# MCU.net
KiCad netlist of a schematic drawn in Altium Designer
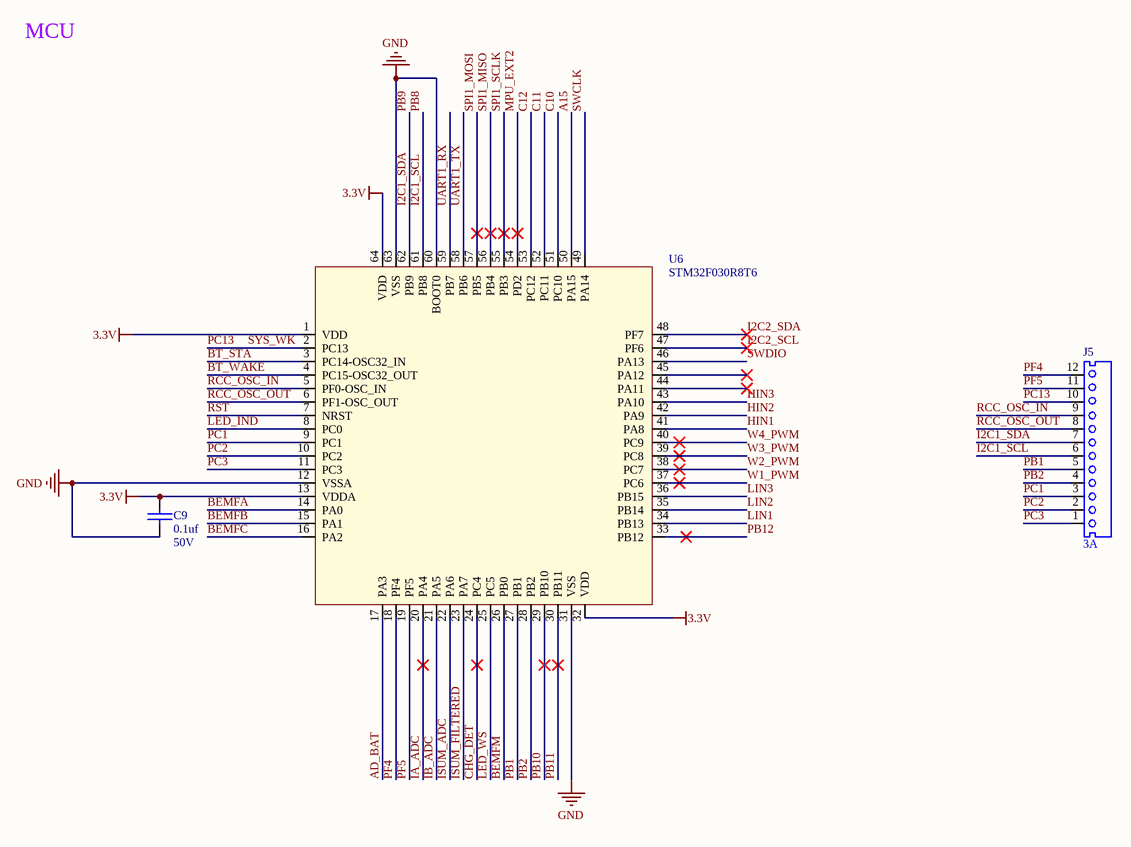
[diagram p0: MCU.SchDoc]

(export (version "E")
  (design (tool "Eeschema 10.0.6"))
  (components
    (comp (ref "C9")
      (value "0.1uf")
      (footprint "CAPC0603-RW")
      (description "GP CHIP CAP 0.015uF 50V 10% 0603 TYPE X7R")
      (fields
        (field (name "TOLERANCE") "10%")
        (field (name "VOLTAGE") "50V")
        (field (name "Comment") "PXL456470-1530")
      )
      (libsource (lib "P-Capacitors") (part "CAP0603 0.015uF 50V 10%"))
    )
    (comp (ref "J5")
      (value "T690300029300")
      (footprint "CONN 12P PH=2.5 ST HAA250A-12A")
      (description "CONNECTOR 12 PIN P:2.5MM P2.54-12 K")
      (fields
        (field (name "MFG") "金科基")
        (field (name "MFG PART") "HAA250A-12A")
        (field (name "CURRENT") "3A")
        (field (name "CREATE_NAME") "Nathan")
      )
      (libsource (lib "C-Connector") (part "CONN 12P PH=2.5 ST HAA250A-12A"))
    )
    (comp (ref "U6")
      (value "T610300097225")
      (footprint "QFP50P1200X1200X160-64N")
      (description "MCU STM32F030RCT6TR LQFP64 ST K")
      (fields
        (field (name "MFG") "ST     (STM意法半導體)")
        (field (name "MFG PART") "STM32F030R8T6")
        (field (name "CREATE_NAME") "Nathan")
      )
      (libsource (lib "R-Semiconductors") (part "STM32F030RCT6TR"))
    )
  )
  (nets
    (net (code "1") (name "/A15") (class "Default")
      (node (ref "U6") (pin "50") (pinfunction "PA15_50") (pintype "passive"))
    )
    (net (code "2") (name "/AD_BAT") (class "Default")
      (node (ref "U6") (pin "17") (pinfunction "PA3_17") (pintype "passive"))
    )
    (net (code "3") (name "/BEMFA") (class "Default")
      (node (ref "U6") (pin "14") (pinfunction "PA0_14") (pintype "passive"))
    )
    (net (code "4") (name "/BEMFB") (class "Default")
      (node (ref "U6") (pin "15") (pinfunction "PA1_15") (pintype "passive"))
    )
    (net (code "5") (name "/BEMFC") (class "Default")
      (node (ref "U6") (pin "16") (pinfunction "PA2_16") (pintype "passive"))
    )
    (net (code "6") (name "/BEMFM") (class "Default")
      (node (ref "U6") (pin "26") (pinfunction "PB0_26") (pintype "passive"))
    )
    (net (code "7") (name "/BT_STA") (class "Default")
      (node (ref "U6") (pin "3") (pinfunction "PC14-OSC32_IN_3") (pintype "passive"))
    )
    (net (code "8") (name "/BT_WAKE") (class "Default")
      (node (ref "U6") (pin "4") (pinfunction "PC15-OSC32_OUT_4") (pintype "passive"))
    )
    (net (code "9") (name "/C10") (class "Default")
      (node (ref "U6") (pin "51") (pinfunction "PC10_51") (pintype "passive"))
    )
    (net (code "10") (name "/C11") (class "Default")
      (node (ref "U6") (pin "52") (pinfunction "PC11_52") (pintype "passive"))
    )
    (net (code "11") (name "/C12") (class "Default")
      (node (ref "U6") (pin "53") (pinfunction "PC12_53") (pintype "passive"))
    )
    (net (code "12") (name "/CHG_DET") (class "Default")
      (node (ref "U6") (pin "24") (pinfunction "PC4_24") (pintype "passive"))
    )
    (net (code "13") (name "/HIN1") (class "Default")
      (node (ref "U6") (pin "41") (pinfunction "PA8_41") (pintype "passive"))
    )
    (net (code "14") (name "/HIN2") (class "Default")
      (node (ref "U6") (pin "42") (pinfunction "PA9_42") (pintype "passive"))
    )
    (net (code "15") (name "/HIN3") (class "Default")
      (node (ref "U6") (pin "43") (pinfunction "PA10_43") (pintype "passive"))
    )
    (net (code "16") (name "/I2C1_SCL") (class "Default")
      (node (ref "J5") (pin "6") (pinfunction "6_6") (pintype "passive"))
      (node (ref "U6") (pin "61") (pinfunction "PB8_61") (pintype "passive"))
    )
    (net (code "17") (name "/I2C1_SDA") (class "Default")
      (node (ref "J5") (pin "7") (pinfunction "7_7") (pintype "passive"))
      (node (ref "U6") (pin "62") (pinfunction "PB9_62") (pintype "passive"))
    )
    (net (code "18") (name "/I2C2_SCL") (class "Default")
      (node (ref "U6") (pin "47") (pinfunction "PF6_47") (pintype "passive+no_connect"))
    )
    (net (code "19") (name "/I2C2_SDA") (class "Default")
      (node (ref "U6") (pin "48") (pinfunction "PF7_48") (pintype "passive+no_connect"))
    )
    (net (code "20") (name "/IA_ADC") (class "Default")
      (node (ref "U6") (pin "20") (pinfunction "PA4_20") (pintype "passive"))
    )
    (net (code "21") (name "/IB_ADC") (class "Default")
      (node (ref "U6") (pin "21") (pinfunction "PA5_21") (pintype "passive"))
    )
    (net (code "22") (name "/ISUM_ADC") (class "Default")
      (node (ref "U6") (pin "22") (pinfunction "PA6_22") (pintype "passive"))
    )
    (net (code "23") (name "/ISUM_FILTERED") (class "Default")
      (node (ref "U6") (pin "23") (pinfunction "PA7_23") (pintype "passive"))
    )
    (net (code "24") (name "/LED_IND") (class "Default")
      (node (ref "U6") (pin "8") (pinfunction "PC0_8") (pintype "passive"))
    )
    (net (code "25") (name "/LED_WS") (class "Default")
      (node (ref "U6") (pin "25") (pinfunction "PC5_25") (pintype "passive"))
    )
    (net (code "26") (name "/LIN1") (class "Default")
      (node (ref "U6") (pin "34") (pinfunction "PB13_34") (pintype "passive"))
    )
    (net (code "27") (name "/LIN2") (class "Default")
      (node (ref "U6") (pin "35") (pinfunction "PB14_35") (pintype "passive"))
    )
    (net (code "28") (name "/LIN3") (class "Default")
      (node (ref "U6") (pin "36") (pinfunction "PB15_36") (pintype "passive"))
    )
    (net (code "29") (name "/MPU_EXT2") (class "Default")
      (node (ref "U6") (pin "54") (pinfunction "PD2_54") (pintype "passive"))
    )
    (net (code "30") (name "/PB1") (class "Default")
      (node (ref "J5") (pin "5") (pinfunction "5_5") (pintype "passive"))
      (node (ref "U6") (pin "27") (pinfunction "PB1_27") (pintype "passive"))
    )
    (net (code "31") (name "/PB2") (class "Default")
      (node (ref "J5") (pin "4") (pinfunction "4_4") (pintype "passive"))
      (node (ref "U6") (pin "28") (pinfunction "PB2_28") (pintype "passive"))
    )
    (net (code "32") (name "/PB10") (class "Default")
      (node (ref "U6") (pin "29") (pinfunction "PB10_29") (pintype "passive"))
    )
    (net (code "33") (name "/PB11") (class "Default")
      (node (ref "U6") (pin "30") (pinfunction "PB11_30") (pintype "passive"))
    )
    (net (code "34") (name "/PB12") (class "Default")
      (node (ref "U6") (pin "33") (pinfunction "PB12_33") (pintype "passive"))
    )
    (net (code "35") (name "/PC1") (class "Default")
      (node (ref "J5") (pin "3") (pinfunction "3_3") (pintype "passive"))
      (node (ref "U6") (pin "9") (pinfunction "PC1_9") (pintype "passive"))
    )
    (net (code "36") (name "/PC2") (class "Default")
      (node (ref "J5") (pin "2") (pinfunction "2_2") (pintype "passive"))
      (node (ref "U6") (pin "10") (pinfunction "PC2_10") (pintype "passive"))
    )
    (net (code "37") (name "/PC3") (class "Default")
      (node (ref "J5") (pin "1") (pinfunction "1_1") (pintype "passive"))
      (node (ref "U6") (pin "11") (pinfunction "PC3_11") (pintype "passive"))
    )
    (net (code "38") (name "/PC13") (class "Default")
      (node (ref "J5") (pin "10") (pinfunction "10_10") (pintype "passive"))
      (node (ref "U6") (pin "2") (pinfunction "PC13_2") (pintype "passive"))
    )
    (net (code "39") (name "/PF4") (class "Default")
      (node (ref "J5") (pin "12") (pinfunction "12_12") (pintype "passive"))
      (node (ref "U6") (pin "18") (pinfunction "PF4_18") (pintype "passive"))
    )
    (net (code "40") (name "/PF5") (class "Default")
      (node (ref "J5") (pin "11") (pinfunction "11_11") (pintype "passive"))
      (node (ref "U6") (pin "19") (pinfunction "PF5_19") (pintype "passive"))
    )
    (net (code "41") (name "/RCC_OSC_IN") (class "Default")
      (node (ref "J5") (pin "9") (pinfunction "9_9") (pintype "passive"))
      (node (ref "U6") (pin "5") (pinfunction "PF0-OSC_IN_5") (pintype "passive"))
    )
    (net (code "42") (name "/RCC_OSC_OUT") (class "Default")
      (node (ref "J5") (pin "8") (pinfunction "8_8") (pintype "passive"))
      (node (ref "U6") (pin "6") (pinfunction "PF1-OSC_OUT_6") (pintype "passive"))
    )
    (net (code "43") (name "/RST") (class "Default")
      (node (ref "U6") (pin "7") (pinfunction "NRST_7") (pintype "passive"))
    )
    (net (code "44") (name "/SPI1_MISO") (class "Default")
      (node (ref "U6") (pin "56") (pinfunction "PB4_56") (pintype "passive"))
    )
    (net (code "45") (name "/SPI1_MOSI") (class "Default")
      (node (ref "U6") (pin "57") (pinfunction "PB5_57") (pintype "passive"))
    )
    (net (code "46") (name "/SPI1_SCLK") (class "Default")
      (node (ref "U6") (pin "55") (pinfunction "PB3_55") (pintype "passive"))
    )
    (net (code "47") (name "/SWCLK") (class "Default")
      (node (ref "U6") (pin "49") (pinfunction "PA14_49") (pintype "passive"))
    )
    (net (code "48") (name "/SWDIO") (class "Default")
      (node (ref "U6") (pin "46") (pinfunction "PA13_46") (pintype "passive"))
    )
    (net (code "49") (name "/UART1_RX") (class "Default")
      (node (ref "U6") (pin "59") (pinfunction "PB7_59") (pintype "passive"))
    )
    (net (code "50") (name "/UART1_TX") (class "Default")
      (node (ref "U6") (pin "58") (pinfunction "PB6_58") (pintype "passive"))
    )
    (net (code "51") (name "/W1_PWM") (class "Default")
      (node (ref "U6") (pin "37") (pinfunction "PC6_37") (pintype "passive"))
    )
    (net (code "52") (name "/W2_PWM") (class "Default")
      (node (ref "U6") (pin "38") (pinfunction "PC7_38") (pintype "passive"))
    )
    (net (code "53") (name "/W3_PWM") (class "Default")
      (node (ref "U6") (pin "39") (pinfunction "PC8_39") (pintype "passive"))
    )
    (net (code "54") (name "/W4_PWM") (class "Default")
      (node (ref "U6") (pin "40") (pinfunction "PC9_40") (pintype "passive"))
    )
    (net (code "55") (name "3.3V") (class "Default")
      (node (ref "C9") (pin "2") (pinfunction "2_2") (pintype "passive"))
      (node (ref "U6") (pin "1") (pinfunction "VDD_1") (pintype "passive"))
      (node (ref "U6") (pin "13") (pinfunction "VDDA_13") (pintype "passive"))
      (node (ref "U6") (pin "32") (pinfunction "VDD_32") (pintype "passive"))
      (node (ref "U6") (pin "64") (pinfunction "VDD_64") (pintype "passive"))
    )
    (net (code "56") (name "GND") (class "Default")
      (node (ref "C9") (pin "1") (pinfunction "1_1") (pintype "passive"))
      (node (ref "U6") (pin "12") (pinfunction "VSSA_12") (pintype "passive"))
      (node (ref "U6") (pin "31") (pinfunction "VSS_31") (pintype "passive"))
      (node (ref "U6") (pin "60") (pinfunction "BOOT0_60") (pintype "passive"))
      (node (ref "U6") (pin "63") (pinfunction "VSS_63") (pintype "passive"))
    )
    (net (code "57") (name "unconnected-(U6-PA11-Pad44)") (class "Default")
      (node (ref "U6") (pin "44") (pinfunction "PA11_44") (pintype "passive+no_connect"))
    )
    (net (code "58") (name "unconnected-(U6-PA12-Pad45)") (class "Default")
      (node (ref "U6") (pin "45") (pinfunction "PA12_45") (pintype "passive+no_connect"))
    )
  )
)
